# Sch_Add.net
KiCad netlist of a schematic drawn in Altium Designer
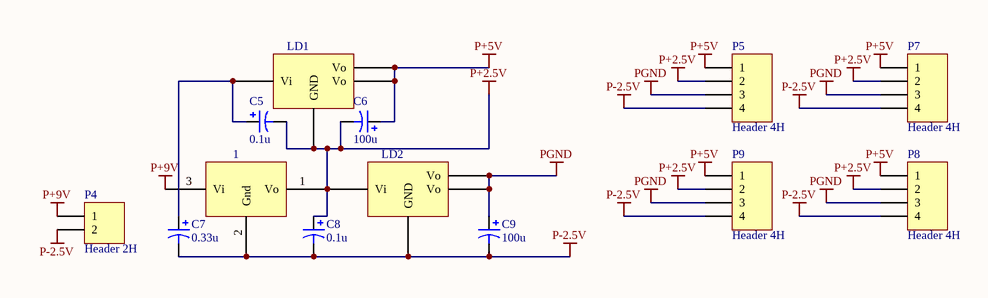
[diagram p0: Sch_Add.SchDoc]

(export (version "E")
  (design (tool "Eeschema 10.0.6"))
  (components
    (comp (ref "1") (value "7805") (footprint "TO-92") (libsource (lib "tlv3542") (part "7805")))
    (comp (ref "C5")
      (value "0.1u")
      (footprint "C0805")
      (description "Polarized Capacitor (Surface Mount)")
      (fields (field (name "Comment") "Cap Pol3") (field (name "PUBLISHER") "Altium Limited"))
      (libsource (lib "Miscellaneous Devices") (part "Cap Pol3"))
    )
    (comp (ref "C6")
      (value "100u")
      (footprint "C0805")
      (description "Polarized Capacitor (Surface Mount)")
      (fields (field (name "Comment") "Cap Pol3") (field (name "PUBLISHER") "Altium Limited"))
      (libsource (lib "Miscellaneous Devices") (part "Cap Pol3"))
    )
    (comp (ref "C7")
      (value "0.33u")
      (footprint "C0805")
      (description "Polarized Capacitor (Surface Mount)")
      (fields (field (name "Comment") "Cap Pol3") (field (name "PUBLISHER") "Altium Limited"))
      (libsource (lib "Miscellaneous Devices") (part "Cap Pol3"))
    )
    (comp (ref "C8")
      (value "0.1u")
      (footprint "C0805")
      (description "Polarized Capacitor (Surface Mount)")
      (fields (field (name "Comment") "Cap Pol3") (field (name "PUBLISHER") "Altium Limited"))
      (libsource (lib "Miscellaneous Devices") (part "Cap Pol3"))
    )
    (comp (ref "C9")
      (value "100u")
      (footprint "C0805")
      (description "Polarized Capacitor (Surface Mount)")
      (fields (field (name "Comment") "Cap Pol3") (field (name "PUBLISHER") "Altium Limited"))
      (libsource (lib "Miscellaneous Devices") (part "Cap Pol3"))
    )
    (comp (ref "LD1")
      (value "LD1117")
      (footprint "SOT230P700X180-4N")
      (libsource (lib "tlv3542") (part "LD1117"))
    )
    (comp (ref "LD2")
      (value "LD1117")
      (footprint "SOT230P700X180-4N")
      (libsource (lib "tlv3542") (part "LD1117"))
    )
    (comp (ref "P4")
      (value "Header 2H")
      (footprint "HDR1X2H")
      (description "Header, 2-Pin, Right Angle")
      (fields (field (name "PUBLISHER") "Altium Limited"))
      (libsource (lib "Miscellaneous Connectors") (part "Header 2H"))
    )
    (comp (ref "P5")
      (value "Header 4H")
      (footprint "HDR1X4H")
      (description "Header, 4-Pin, Right Angle")
      (fields (field (name "PUBLISHER") "Altium Limited"))
      (libsource (lib "Miscellaneous Connectors") (part "Header 4H"))
    )
    (comp (ref "P7")
      (value "Header 4H")
      (footprint "HDR1X4H")
      (description "Header, 4-Pin, Right Angle")
      (fields (field (name "PUBLISHER") "Altium Limited"))
      (libsource (lib "Miscellaneous Connectors") (part "Header 4H"))
    )
    (comp (ref "P8")
      (value "Header 4H")
      (footprint "HDR1X4H")
      (description "Header, 4-Pin, Right Angle")
      (fields (field (name "PUBLISHER") "Altium Limited"))
      (libsource (lib "Miscellaneous Connectors") (part "Header 4H"))
    )
    (comp (ref "P9")
      (value "Header 4H")
      (footprint "HDR1X4H")
      (description "Header, 4-Pin, Right Angle")
      (fields (field (name "PUBLISHER") "Altium Limited"))
      (libsource (lib "Miscellaneous Connectors") (part "Header 4H"))
    )
  )
  (nets
    (net (code "1") (name "Net-(LD1-Vi)") (class "Default")
      (node (ref "C5") (pin "1") (pinfunction "1_1") (pintype "passive"))
      (node (ref "C7") (pin "1") (pinfunction "1_1") (pintype "passive"))
      (node (ref "LD1") (pin "3") (pinfunction "Vi_3") (pintype "passive"))
    )
    (net (code "2") (name "P+2.5V") (class "Default")
      (node (ref "1") (pin "1") (pinfunction "Vo_1") (pintype "passive"))
      (node (ref "C5") (pin "2") (pinfunction "2_2") (pintype "passive"))
      (node (ref "C6") (pin "2") (pinfunction "2_2") (pintype "passive"))
      (node (ref "C8") (pin "1") (pinfunction "1_1") (pintype "passive"))
      (node (ref "LD1") (pin "1") (pinfunction "GND_1") (pintype "passive"))
      (node (ref "LD2") (pin "3") (pinfunction "Vi_3") (pintype "passive"))
      (node (ref "P5") (pin "2") (pinfunction "2_2") (pintype "passive"))
      (node (ref "P7") (pin "2") (pinfunction "2_2") (pintype "passive"))
      (node (ref "P8") (pin "2") (pinfunction "2_2") (pintype "passive"))
      (node (ref "P9") (pin "2") (pinfunction "2_2") (pintype "passive"))
    )
    (net (code "3") (name "P+5V") (class "Default")
      (node (ref "C6") (pin "1") (pinfunction "1_1") (pintype "passive"))
      (node (ref "LD1") (pin "2") (pinfunction "Vo_2") (pintype "passive"))
      (node (ref "LD1") (pin "4") (pinfunction "Vo_4") (pintype "passive"))
      (node (ref "P5") (pin "1") (pinfunction "1_1") (pintype "passive"))
      (node (ref "P7") (pin "1") (pinfunction "1_1") (pintype "passive"))
      (node (ref "P8") (pin "1") (pinfunction "1_1") (pintype "passive"))
      (node (ref "P9") (pin "1") (pinfunction "1_1") (pintype "passive"))
    )
    (net (code "4") (name "P+9V") (class "Default")
      (node (ref "1") (pin "3") (pinfunction "Vi_3") (pintype "passive"))
      (node (ref "P4") (pin "1") (pinfunction "1_1") (pintype "passive"))
    )
    (net (code "5") (name "P-2.5V") (class "Default")
      (node (ref "1") (pin "2") (pinfunction "Gnd_2") (pintype "passive"))
      (node (ref "C7") (pin "2") (pinfunction "2_2") (pintype "passive"))
      (node (ref "C8") (pin "2") (pinfunction "2_2") (pintype "passive"))
      (node (ref "C9") (pin "2") (pinfunction "2_2") (pintype "passive"))
      (node (ref "LD2") (pin "1") (pinfunction "GND_1") (pintype "passive"))
      (node (ref "P4") (pin "2") (pinfunction "2_2") (pintype "passive"))
      (node (ref "P5") (pin "4") (pinfunction "4_4") (pintype "passive"))
      (node (ref "P7") (pin "4") (pinfunction "4_4") (pintype "passive"))
      (node (ref "P8") (pin "4") (pinfunction "4_4") (pintype "passive"))
      (node (ref "P9") (pin "4") (pinfunction "4_4") (pintype "passive"))
    )
    (net (code "6") (name "PGND") (class "Default")
      (node (ref "C9") (pin "1") (pinfunction "1_1") (pintype "passive"))
      (node (ref "LD2") (pin "2") (pinfunction "Vo_2") (pintype "passive"))
      (node (ref "LD2") (pin "4") (pinfunction "Vo_4") (pintype "passive"))
      (node (ref "P5") (pin "3") (pinfunction "3_3") (pintype "passive"))
      (node (ref "P7") (pin "3") (pinfunction "3_3") (pintype "passive"))
      (node (ref "P8") (pin "3") (pinfunction "3_3") (pintype "passive"))
      (node (ref "P9") (pin "3") (pinfunction "3_3") (pintype "passive"))
    )
  )
)
